# SHDN21-S03-V00-DACResistors.net
KiCad netlist of a schematic drawn in Altium Designer
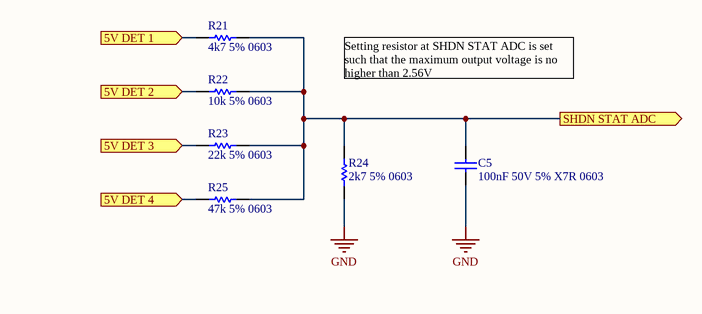
[diagram p0: SHDN21-S03-V00-DACResistors.SchDoc]

(export (version "E")
  (design (tool "Eeschema 10.0.6"))
  (components
    (comp (ref "C5")
      (value "100nF 50V 5% X7R 0603")
      (footprint "Cap_Ceramic_0603")
      (description "Capacitor, Ceramic, SMD, 100nF, 50V, 5%, X7R, 0603")
      (libsource (lib "StandardCapacitors") (part "100nF 50V 5% X7R 0603"))
    )
    (comp (ref "R21")
      (value "4k7 5% 0603")
      (footprint "Res_ThinFilm_0603")
      (description "Resistor, SMD, 4k7, 0.1W, 5%, 0603")
      (libsource (lib "StandardResistors") (part "4k7 5% 0603"))
    )
    (comp (ref "R22")
      (value "10k 5% 0603")
      (footprint "Res_ThinFilm_0603")
      (description "Resistor, SMD, 10k, 0.1W, 5%, 0603")
      (libsource (lib "StandardResistors") (part "10k 5% 0603"))
    )
    (comp (ref "R23")
      (value "22k 5% 0603")
      (footprint "Res_ThinFilm_0603")
      (description "Resistor, SMD, 22k, 0.1W, 5%, 0603")
      (libsource (lib "StandardResistors") (part "22k 5% 0603"))
    )
    (comp (ref "R24")
      (value "2k7 5% 0603")
      (footprint "Res_ThinFilm_0603")
      (description "Resistor, SMD, 2k7, 0.1W, 5%, 0603")
      (libsource (lib "StandardResistors") (part "2k7 5% 0603"))
    )
    (comp (ref "R25")
      (value "47k 5% 0603")
      (footprint "Res_ThinFilm_0603")
      (description "Resistor, SMD, 47k, 0.1W, 5%, 0603")
      (libsource (lib "StandardResistors") (part "47k 5% 0603"))
    )
  )
  (nets
    (net (code "1") (name "/5V DET 1") (class "Default")
      (node (ref "R21") (pin "1") (pinfunction "1_1") (pintype "passive"))
    )
    (net (code "2") (name "/5V DET 2") (class "Default")
      (node (ref "R22") (pin "1") (pinfunction "1_1") (pintype "passive"))
    )
    (net (code "3") (name "/5V DET 3") (class "Default")
      (node (ref "R23") (pin "1") (pinfunction "1_1") (pintype "passive"))
    )
    (net (code "4") (name "/5V DET 4") (class "Default")
      (node (ref "R25") (pin "1") (pinfunction "1_1") (pintype "passive"))
    )
    (net (code "5") (name "/SHDN STAT ADC") (class "Default")
      (node (ref "C5") (pin "2") (pinfunction "2_2") (pintype "passive"))
      (node (ref "R21") (pin "2") (pinfunction "2_2") (pintype "passive"))
      (node (ref "R22") (pin "2") (pinfunction "2_2") (pintype "passive"))
      (node (ref "R23") (pin "2") (pinfunction "2_2") (pintype "passive"))
      (node (ref "R24") (pin "2") (pinfunction "2_2") (pintype "passive"))
      (node (ref "R25") (pin "2") (pinfunction "2_2") (pintype "passive"))
    )
    (net (code "6") (name "GND") (class "Default")
      (node (ref "C5") (pin "1") (pinfunction "1_1") (pintype "passive"))
      (node (ref "R24") (pin "1") (pinfunction "1_1") (pintype "passive"))
    )
  )
)
